# NanoRemotev2.net
KiCad netlist of a schematic drawn in EAGLE
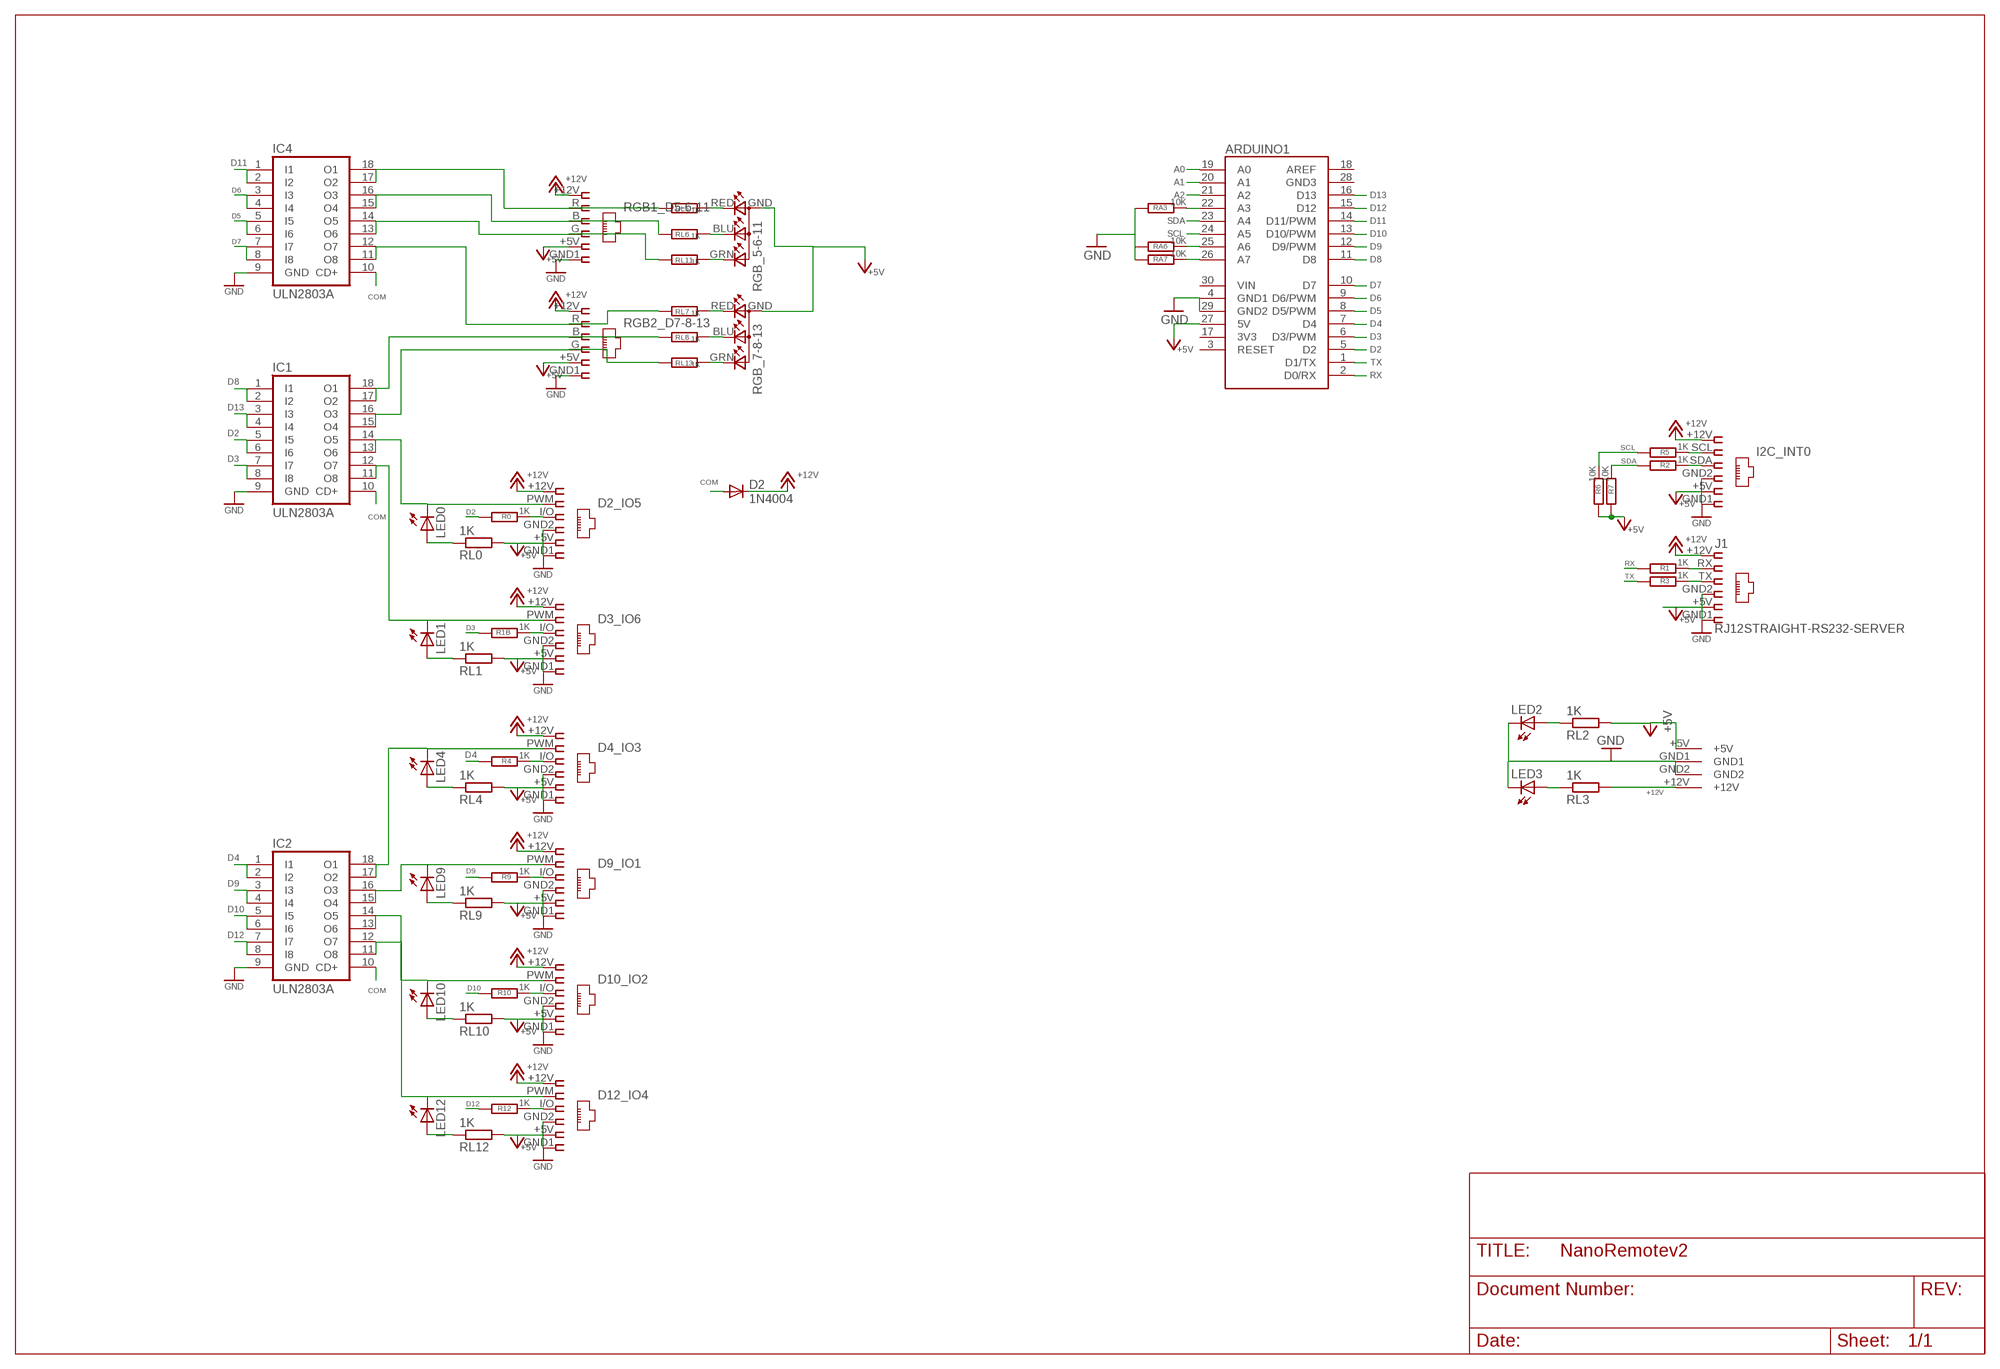
[diagram p0: schematic, sheet 1]

(export (version "E")
  (design (tool "Eeschema 10.0.6"))
  (components
    (comp (ref "ARDUINO1")
      (value "ARDUINO_NANO")
      (footprint "eagle-import:ARDUINO_NANO")
      (libsource (lib "eagle-import") (part "ARDUINO_NANO"))
    )
    (comp (ref "D2")
      (value "1N4004")
      (footprint "eagle-import:DO41-10")
      (libsource (lib "eagle-import") (part "1N4004"))
    )
    (comp (ref "D2_IO5")
      (value "IO5")
      (footprint "eagle-import:RJ12-STRAIGHT")
      (libsource (lib "eagle-import") (part "RJ12STRAIGHT"))
    )
    (comp (ref "D3_IO6")
      (value "IO6")
      (footprint "eagle-import:RJ12-STRAIGHT")
      (libsource (lib "eagle-import") (part "RJ12STRAIGHT"))
    )
    (comp (ref "D4_IO3")
      (value "IO3")
      (footprint "eagle-import:RJ12-STRAIGHT")
      (libsource (lib "eagle-import") (part "RJ12STRAIGHT"))
    )
    (comp (ref "D9_IO1")
      (value "IO1")
      (footprint "eagle-import:RJ12-STRAIGHT")
      (libsource (lib "eagle-import") (part "RJ12STRAIGHT"))
    )
    (comp (ref "D10_IO2")
      (value "IO2")
      (footprint "eagle-import:RJ12-STRAIGHT")
      (libsource (lib "eagle-import") (part "RJ12STRAIGHT"))
    )
    (comp (ref "D12_IO4")
      (value "IO4")
      (footprint "eagle-import:RJ12-STRAIGHT")
      (libsource (lib "eagle-import") (part "RJ12STRAIGHT"))
    )
    (comp (ref "I2C_INT0")
      (value "I2C")
      (footprint "eagle-import:RJ12-STRAIGHT-I2C")
      (libsource (lib "eagle-import") (part "RJ12STRAIGHT-I2C"))
    )
    (comp (ref "IC1")
      (value "ULN2803A")
      (footprint "eagle-import:SO18W")
      (libsource (lib "eagle-import") (part "ULN2803A"))
    )
    (comp (ref "IC2")
      (value "ULN2803A")
      (footprint "eagle-import:SO18W")
      (libsource (lib "eagle-import") (part "ULN2803A"))
    )
    (comp (ref "IC4")
      (value "ULN2803A")
      (footprint "eagle-import:SO18W")
      (libsource (lib "eagle-import") (part "ULN2803A"))
    )
    (comp (ref "J1")
      (value "RJ12STRAIGHT-RS232-SERVER")
      (footprint "eagle-import:RJ12-STRAIGHT-RS232")
      (libsource (lib "eagle-import") (part "RJ12STRAIGHT-RS232-SERVER"))
    )
    (comp (ref "LED0")
      (value "LED3MM")
      (footprint "eagle-import:LED3MM")
      (libsource (lib "eagle-import") (part "LED3MM"))
    )
    (comp (ref "LED1")
      (value "LED3MM")
      (footprint "eagle-import:LED3MM")
      (libsource (lib "eagle-import") (part "LED3MM"))
    )
    (comp (ref "LED2")
      (value "LED3MM")
      (footprint "eagle-import:LED3MM")
      (libsource (lib "eagle-import") (part "LED3MM"))
    )
    (comp (ref "LED3")
      (value "LED3MM")
      (footprint "eagle-import:LED3MM")
      (libsource (lib "eagle-import") (part "LED3MM"))
    )
    (comp (ref "LED4")
      (value "LED3MM")
      (footprint "eagle-import:LED3MM")
      (libsource (lib "eagle-import") (part "LED3MM"))
    )
    (comp (ref "LED9")
      (value "LED3MM")
      (footprint "eagle-import:LED3MM")
      (libsource (lib "eagle-import") (part "LED3MM"))
    )
    (comp (ref "LED10")
      (value "LED3MM")
      (footprint "eagle-import:LED3MM")
      (libsource (lib "eagle-import") (part "LED3MM"))
    )
    (comp (ref "LED12")
      (value "LED3MM")
      (footprint "eagle-import:LED3MM")
      (libsource (lib "eagle-import") (part "LED3MM"))
    )
    (comp (ref "R0")
      (value "1K")
      (footprint "eagle-import:M1206")
      (libsource (lib "eagle-import") (part "R-EU_M1206"))
    )
    (comp (ref "R1")
      (value "1K")
      (footprint "eagle-import:M1206")
      (libsource (lib "eagle-import") (part "R-EU_M1206"))
    )
    (comp (ref "R1B")
      (value "1K")
      (footprint "eagle-import:M1206")
      (libsource (lib "eagle-import") (part "R-EU_M1206"))
    )
    (comp (ref "R2")
      (value "1K")
      (footprint "eagle-import:M1206")
      (libsource (lib "eagle-import") (part "R-EU_M1206"))
    )
    (comp (ref "R3")
      (value "1K")
      (footprint "eagle-import:M1206")
      (libsource (lib "eagle-import") (part "R-EU_M1206"))
    )
    (comp (ref "R4")
      (value "1K")
      (footprint "eagle-import:M1206")
      (libsource (lib "eagle-import") (part "R-EU_M1206"))
    )
    (comp (ref "R5")
      (value "1K")
      (footprint "eagle-import:M1206")
      (libsource (lib "eagle-import") (part "R-EU_M1206"))
    )
    (comp (ref "R6")
      (value "10K")
      (footprint "eagle-import:M1206")
      (libsource (lib "eagle-import") (part "R-EU_M1206"))
    )
    (comp (ref "R7")
      (value "10K")
      (footprint "eagle-import:M1206")
      (libsource (lib "eagle-import") (part "R-EU_M1206"))
    )
    (comp (ref "R9")
      (value "1K")
      (footprint "eagle-import:M1206")
      (libsource (lib "eagle-import") (part "R-EU_M1206"))
    )
    (comp (ref "R10")
      (value "1K")
      (footprint "eagle-import:M1206")
      (libsource (lib "eagle-import") (part "R-EU_M1206"))
    )
    (comp (ref "R12")
      (value "1K")
      (footprint "eagle-import:M1206")
      (libsource (lib "eagle-import") (part "R-EU_M1206"))
    )
    (comp (ref "RA3")
      (value "10K")
      (footprint "eagle-import:M1206")
      (libsource (lib "eagle-import") (part "R-EU_M1206"))
    )
    (comp (ref "RA6")
      (value "10K")
      (footprint "eagle-import:M1206")
      (libsource (lib "eagle-import") (part "R-EU_M1206"))
    )
    (comp (ref "RA7")
      (value "10K")
      (footprint "eagle-import:M1206")
      (libsource (lib "eagle-import") (part "R-EU_M1206"))
    )
    (comp (ref "RGB1_D5-6-11")
      (value "RGB1")
      (footprint "eagle-import:RJ12-STRAIGHT-RGB")
      (libsource (lib "eagle-import") (part "RJ12STRAIGHT-RGB"))
    )
    (comp (ref "RGB2_D7-8-13")
      (value "RGB2")
      (footprint "eagle-import:RJ12-STRAIGHT-RGB")
      (libsource (lib "eagle-import") (part "RJ12STRAIGHT-RGB"))
    )
    (comp (ref "RGB_5-6-11")
      (value "TOPLED-3")
      (footprint "eagle-import:LED-TRICOLOR-THROUGHHOLE")
      (libsource (lib "eagle-import") (part "TOPLED-3"))
    )
    (comp (ref "RGB_7-8-13")
      (value "TOPLED-3")
      (footprint "eagle-import:LED-TRICOLOR-THROUGHHOLE")
      (libsource (lib "eagle-import") (part "TOPLED-3"))
    )
    (comp (ref "RL0")
      (value "1K")
      (footprint "eagle-import:M1206")
      (libsource (lib "eagle-import") (part "R-EU_M1206"))
    )
    (comp (ref "RL1")
      (value "1K")
      (footprint "eagle-import:M1206")
      (libsource (lib "eagle-import") (part "R-EU_M1206"))
    )
    (comp (ref "RL2")
      (value "1K")
      (footprint "eagle-import:M1206")
      (libsource (lib "eagle-import") (part "R-EU_M1206"))
    )
    (comp (ref "RL3")
      (value "1K")
      (footprint "eagle-import:M1206")
      (libsource (lib "eagle-import") (part "R-EU_M1206"))
    )
    (comp (ref "RL4")
      (value "1K")
      (footprint "eagle-import:M1206")
      (libsource (lib "eagle-import") (part "R-EU_M1206"))
    )
    (comp (ref "RL5")
      (value "1K")
      (footprint "eagle-import:M1206")
      (libsource (lib "eagle-import") (part "R-EU_M1206"))
    )
    (comp (ref "RL6")
      (value "1K")
      (footprint "eagle-import:M1206")
      (libsource (lib "eagle-import") (part "R-EU_M1206"))
    )
    (comp (ref "RL7")
      (value "1K")
      (footprint "eagle-import:M1206")
      (libsource (lib "eagle-import") (part "R-EU_M1206"))
    )
    (comp (ref "RL8")
      (value "1K")
      (footprint "eagle-import:M1206")
      (libsource (lib "eagle-import") (part "R-EU_M1206"))
    )
    (comp (ref "RL9")
      (value "1K")
      (footprint "eagle-import:M1206")
      (libsource (lib "eagle-import") (part "R-EU_M1206"))
    )
    (comp (ref "RL10")
      (value "1K")
      (footprint "eagle-import:M1206")
      (libsource (lib "eagle-import") (part "R-EU_M1206"))
    )
    (comp (ref "RL11")
      (value "1K")
      (footprint "eagle-import:M1206")
      (libsource (lib "eagle-import") (part "R-EU_M1206"))
    )
    (comp (ref "RL12")
      (value "1K")
      (footprint "eagle-import:M1206")
      (libsource (lib "eagle-import") (part "R-EU_M1206"))
    )
    (comp (ref "RL13")
      (value "1K")
      (footprint "eagle-import:M1206")
      (libsource (lib "eagle-import") (part "R-EU_M1206"))
    )
    (comp (ref "U$1")
      (value "KPJX-4S-S")
      (footprint "eagle-import:KPJX-4S-S")
      (libsource (lib "eagle-import") (part "KPJX-4S-S"))
    )
  )
  (nets
    (net (code "1") (name "+5V") (class "Default")
      (node (ref "ARDUINO1") (pin "27") (pinfunction "5V_27") (pintype "power_in"))
      (node (ref "D10_IO2") (pin "+5V") (pinfunction "5_+5V") (pintype "power_in"))
      (node (ref "D12_IO4") (pin "+5V") (pinfunction "5_+5V") (pintype "power_in"))
      (node (ref "D2_IO5") (pin "+5V") (pinfunction "5_+5V") (pintype "power_in"))
      (node (ref "D3_IO6") (pin "+5V") (pinfunction "5_+5V") (pintype "power_in"))
      (node (ref "D4_IO3") (pin "+5V") (pinfunction "5_+5V") (pintype "power_in"))
      (node (ref "D9_IO1") (pin "+5V") (pinfunction "5_+5V") (pintype "power_in"))
      (node (ref "I2C_INT0") (pin "+5V") (pinfunction "5_+5V") (pintype "power_in"))
      (node (ref "J1") (pin "+5V") (pinfunction "5_+5V") (pintype "power_in"))
      (node (ref "R6") (pin "2") (pinfunction "2_2") (pintype "passive"))
      (node (ref "R7") (pin "2") (pinfunction "2_2") (pintype "passive"))
      (node (ref "RGB1_D5-6-11") (pin "+5V") (pinfunction "5_+5V") (pintype "power_in"))
      (node (ref "RGB2_D7-8-13") (pin "+5V") (pinfunction "5_+5V") (pintype "power_in"))
      (node (ref "RGB_5-6-11") (pin "GND") (pinfunction "A2_GND") (pintype "passive"))
      (node (ref "RGB_7-8-13") (pin "GND") (pinfunction "A2_GND") (pintype "passive"))
      (node (ref "RL0") (pin "2") (pinfunction "2_2") (pintype "passive"))
      (node (ref "RL1") (pin "2") (pinfunction "2_2") (pintype "passive"))
      (node (ref "RL10") (pin "2") (pinfunction "2_2") (pintype "passive"))
      (node (ref "RL12") (pin "2") (pinfunction "2_2") (pintype "passive"))
      (node (ref "RL2") (pin "2") (pinfunction "2_2") (pintype "passive"))
      (node (ref "RL4") (pin "2") (pinfunction "2_2") (pintype "passive"))
      (node (ref "RL9") (pin "2") (pinfunction "2_2") (pintype "passive"))
      (node (ref "U$1") (pin "+5V") (pinfunction "+5V_+5V") (pintype "power_in"))
    )
    (net (code "2") (name "+12V") (class "Default")
      (node (ref "D10_IO2") (pin "+12V") (pinfunction "1_+12V") (pintype "power_in"))
      (node (ref "D12_IO4") (pin "+12V") (pinfunction "1_+12V") (pintype "power_in"))
      (node (ref "D2") (pin "C") (pinfunction "C_C") (pintype "passive"))
      (node (ref "D2_IO5") (pin "+12V") (pinfunction "1_+12V") (pintype "power_in"))
      (node (ref "D3_IO6") (pin "+12V") (pinfunction "1_+12V") (pintype "power_in"))
      (node (ref "D4_IO3") (pin "+12V") (pinfunction "1_+12V") (pintype "power_in"))
      (node (ref "D9_IO1") (pin "+12V") (pinfunction "1_+12V") (pintype "power_in"))
      (node (ref "I2C_INT0") (pin "+12V") (pinfunction "1_+12V") (pintype "power_in"))
      (node (ref "J1") (pin "+12V") (pinfunction "1_+12V") (pintype "power_in"))
      (node (ref "RGB1_D5-6-11") (pin "+12V") (pinfunction "1_+12V") (pintype "power_in"))
      (node (ref "RGB2_D7-8-13") (pin "+12V") (pinfunction "1_+12V") (pintype "power_in"))
      (node (ref "RL3") (pin "2") (pinfunction "2_2") (pintype "passive"))
      (node (ref "U$1") (pin "+12V") (pinfunction "+12V_+12V") (pintype "power_in"))
    )
    (net (code "3") (name "/3V3") (class "Default")
      (node (ref "ARDUINO1") (pin "17") (pinfunction "3V3_17") (pintype "power_in"))
    )
    (net (code "4") (name "/A0") (class "Default")
      (node (ref "ARDUINO1") (pin "19") (pinfunction "A0_19") (pintype "bidirectional"))
    )
    (net (code "5") (name "/A1") (class "Default")
      (node (ref "ARDUINO1") (pin "20") (pinfunction "A1_20") (pintype "bidirectional"))
    )
    (net (code "6") (name "/A2") (class "Default")
      (node (ref "ARDUINO1") (pin "21") (pinfunction "A2_21") (pintype "bidirectional"))
    )
    (net (code "7") (name "/COM") (class "Default")
      (node (ref "D2") (pin "A") (pinfunction "A_A") (pintype "passive"))
      (node (ref "IC1") (pin "10") (pinfunction "CD+_10") (pintype "passive"))
      (node (ref "IC2") (pin "10") (pinfunction "CD+_10") (pintype "passive"))
      (node (ref "IC4") (pin "10") (pinfunction "CD+_10") (pintype "passive"))
    )
    (net (code "8") (name "/D2") (class "Default")
      (node (ref "ARDUINO1") (pin "5") (pinfunction "D2_5") (pintype "bidirectional"))
      (node (ref "IC1") (pin "5") (pinfunction "I5_5") (pintype "input"))
      (node (ref "IC1") (pin "6") (pinfunction "I6_6") (pintype "input"))
      (node (ref "R0") (pin "2") (pinfunction "2_2") (pintype "passive"))
    )
    (net (code "9") (name "/D3") (class "Default")
      (node (ref "ARDUINO1") (pin "6") (pinfunction "D3/PWM_6") (pintype "bidirectional"))
      (node (ref "IC1") (pin "7") (pinfunction "I7_7") (pintype "input"))
      (node (ref "IC1") (pin "8") (pinfunction "I8_8") (pintype "input"))
      (node (ref "R1B") (pin "2") (pinfunction "2_2") (pintype "passive"))
    )
    (net (code "10") (name "/D4") (class "Default")
      (node (ref "ARDUINO1") (pin "7") (pinfunction "D4_7") (pintype "bidirectional"))
      (node (ref "IC2") (pin "1") (pinfunction "I1_1") (pintype "input"))
      (node (ref "IC2") (pin "2") (pinfunction "I2_2") (pintype "input"))
      (node (ref "R4") (pin "2") (pinfunction "2_2") (pintype "passive"))
    )
    (net (code "11") (name "/D5") (class "Default")
      (node (ref "ARDUINO1") (pin "8") (pinfunction "D5/PWM_8") (pintype "bidirectional"))
      (node (ref "IC4") (pin "5") (pinfunction "I5_5") (pintype "input"))
      (node (ref "IC4") (pin "6") (pinfunction "I6_6") (pintype "input"))
    )
    (net (code "12") (name "/D6") (class "Default")
      (node (ref "ARDUINO1") (pin "9") (pinfunction "D6/PWM_9") (pintype "bidirectional"))
      (node (ref "IC4") (pin "3") (pinfunction "I3_3") (pintype "input"))
      (node (ref "IC4") (pin "4") (pinfunction "I4_4") (pintype "input"))
    )
    (net (code "13") (name "/D7") (class "Default")
      (node (ref "ARDUINO1") (pin "10") (pinfunction "D7_10") (pintype "bidirectional"))
      (node (ref "IC4") (pin "7") (pinfunction "I7_7") (pintype "input"))
      (node (ref "IC4") (pin "8") (pinfunction "I8_8") (pintype "input"))
    )
    (net (code "14") (name "/D8") (class "Default")
      (node (ref "ARDUINO1") (pin "11") (pinfunction "D8_11") (pintype "bidirectional"))
      (node (ref "IC1") (pin "1") (pinfunction "I1_1") (pintype "input"))
      (node (ref "IC1") (pin "2") (pinfunction "I2_2") (pintype "input"))
    )
    (net (code "15") (name "/D9") (class "Default")
      (node (ref "ARDUINO1") (pin "12") (pinfunction "D9/PWM_12") (pintype "bidirectional"))
      (node (ref "IC2") (pin "3") (pinfunction "I3_3") (pintype "input"))
      (node (ref "IC2") (pin "4") (pinfunction "I4_4") (pintype "input"))
      (node (ref "R9") (pin "2") (pinfunction "2_2") (pintype "passive"))
    )
    (net (code "16") (name "/D10") (class "Default")
      (node (ref "ARDUINO1") (pin "13") (pinfunction "D10/PWM_13") (pintype "bidirectional"))
      (node (ref "IC2") (pin "5") (pinfunction "I5_5") (pintype "input"))
      (node (ref "IC2") (pin "6") (pinfunction "I6_6") (pintype "input"))
      (node (ref "R10") (pin "2") (pinfunction "2_2") (pintype "passive"))
    )
    (net (code "17") (name "/D11") (class "Default")
      (node (ref "ARDUINO1") (pin "14") (pinfunction "D11/PWM_14") (pintype "bidirectional"))
      (node (ref "IC4") (pin "1") (pinfunction "I1_1") (pintype "input"))
      (node (ref "IC4") (pin "2") (pinfunction "I2_2") (pintype "input"))
    )
    (net (code "18") (name "/D12") (class "Default")
      (node (ref "ARDUINO1") (pin "15") (pinfunction "D12_15") (pintype "bidirectional"))
      (node (ref "IC2") (pin "7") (pinfunction "I7_7") (pintype "input"))
      (node (ref "IC2") (pin "8") (pinfunction "I8_8") (pintype "input"))
      (node (ref "R12") (pin "2") (pinfunction "2_2") (pintype "passive"))
    )
    (net (code "19") (name "/D13") (class "Default")
      (node (ref "ARDUINO1") (pin "16") (pinfunction "D13_16") (pintype "bidirectional"))
      (node (ref "IC1") (pin "3") (pinfunction "I3_3") (pintype "input"))
      (node (ref "IC1") (pin "4") (pinfunction "I4_4") (pintype "input"))
    )
    (net (code "20") (name "/RX") (class "Default")
      (node (ref "ARDUINO1") (pin "2") (pinfunction "D0/RX_2") (pintype "bidirectional"))
      (node (ref "R1") (pin "2") (pinfunction "2_2") (pintype "passive"))
    )
    (net (code "21") (name "/SCL") (class "Default")
      (node (ref "ARDUINO1") (pin "24") (pinfunction "A5_24") (pintype "bidirectional"))
      (node (ref "R5") (pin "2") (pinfunction "2_2") (pintype "passive"))
      (node (ref "R6") (pin "1") (pinfunction "1_1") (pintype "passive"))
    )
    (net (code "22") (name "/SDA") (class "Default")
      (node (ref "ARDUINO1") (pin "23") (pinfunction "A4_23") (pintype "bidirectional"))
      (node (ref "R2") (pin "2") (pinfunction "2_2") (pintype "passive"))
      (node (ref "R7") (pin "1") (pinfunction "1_1") (pintype "passive"))
    )
    (net (code "23") (name "/TX") (class "Default")
      (node (ref "ARDUINO1") (pin "1") (pinfunction "D1/TX_1") (pintype "bidirectional"))
      (node (ref "R3") (pin "2") (pinfunction "2_2") (pintype "passive"))
    )
    (net (code "24") (name "GND") (class "Default")
      (node (ref "ARDUINO1") (pin "29") (pinfunction "GND2_29") (pintype "power_in"))
      (node (ref "ARDUINO1") (pin "4") (pinfunction "GND1_4") (pintype "power_in"))
      (node (ref "D10_IO2") (pin "GND1") (pinfunction "6_GND1") (pintype "power_in"))
      (node (ref "D10_IO2") (pin "GND2") (pinfunction "4_GND2") (pintype "power_in"))
      (node (ref "D12_IO4") (pin "GND1") (pinfunction "6_GND1") (pintype "power_in"))
      (node (ref "D12_IO4") (pin "GND2") (pinfunction "4_GND2") (pintype "power_in"))
      (node (ref "D2_IO5") (pin "GND1") (pinfunction "6_GND1") (pintype "power_in"))
      (node (ref "D2_IO5") (pin "GND2") (pinfunction "4_GND2") (pintype "power_in"))
      (node (ref "D3_IO6") (pin "GND1") (pinfunction "6_GND1") (pintype "power_in"))
      (node (ref "D3_IO6") (pin "GND2") (pinfunction "4_GND2") (pintype "power_in"))
      (node (ref "D4_IO3") (pin "GND1") (pinfunction "6_GND1") (pintype "power_in"))
      (node (ref "D4_IO3") (pin "GND2") (pinfunction "4_GND2") (pintype "power_in"))
      (node (ref "D9_IO1") (pin "GND1") (pinfunction "6_GND1") (pintype "power_in"))
      (node (ref "D9_IO1") (pin "GND2") (pinfunction "4_GND2") (pintype "power_in"))
      (node (ref "I2C_INT0") (pin "GND1") (pinfunction "6_GND1") (pintype "power_in"))
      (node (ref "I2C_INT0") (pin "GND2") (pinfunction "4_GND2") (pintype "power_in"))
      (node (ref "IC1") (pin "9") (pinfunction "GND_9") (pintype "power_in"))
      (node (ref "IC2") (pin "9") (pinfunction "GND_9") (pintype "power_in"))
      (node (ref "IC4") (pin "9") (pinfunction "GND_9") (pintype "power_in"))
      (node (ref "J1") (pin "GND1") (pinfunction "6_GND1") (pintype "power_in"))
      (node (ref "J1") (pin "GND2") (pinfunction "4_GND2") (pintype "power_in"))
      (node (ref "LED2") (pin "K") (pinfunction "C_K") (pintype "passive"))
      (node (ref "LED3") (pin "K") (pinfunction "C_K") (pintype "passive"))
      (node (ref "RA3") (pin "2") (pinfunction "2_2") (pintype "passive"))
      (node (ref "RA6") (pin "2") (pinfunction "2_2") (pintype "passive"))
      (node (ref "RA7") (pin "2") (pinfunction "2_2") (pintype "passive"))
      (node (ref "RGB1_D5-6-11") (pin "GND1") (pinfunction "6_GND1") (pintype "power_in"))
      (node (ref "RGB2_D7-8-13") (pin "GND1") (pinfunction "6_GND1") (pintype "power_in"))
      (node (ref "U$1") (pin "GND1") (pinfunction "GND1_GND1") (pintype "input"))
      (node (ref "U$1") (pin "GND2") (pinfunction "GND2_GND2") (pintype "input"))
    )
    (net (code "25") (name "Net-(ARDUINO1-A3)") (class "Default")
      (node (ref "ARDUINO1") (pin "22") (pinfunction "A3_22") (pintype "bidirectional"))
      (node (ref "RA3") (pin "1") (pinfunction "1_1") (pintype "passive"))
    )
    (net (code "26") (name "Net-(ARDUINO1-A6)") (class "Default")
      (node (ref "ARDUINO1") (pin "25") (pinfunction "A6_25") (pintype "bidirectional"))
      (node (ref "RA6") (pin "1") (pinfunction "1_1") (pintype "passive"))
    )
    (net (code "27") (name "Net-(ARDUINO1-A7)") (class "Default")
      (node (ref "ARDUINO1") (pin "26") (pinfunction "A7_26") (pintype "bidirectional"))
      (node (ref "RA7") (pin "1") (pinfunction "1_1") (pintype "passive"))
    )
    (net (code "28") (name "Net-(D2_IO5-2)") (class "Default")
      (node (ref "D2_IO5") (pin "PWM") (pinfunction "2_PWM") (pintype "bidirectional"))
      (node (ref "IC1") (pin "13") (pinfunction "O6_13") (pintype "open_collector"))
      (node (ref "IC1") (pin "14") (pinfunction "O5_14") (pintype "open_collector"))
      (node (ref "LED0") (pin "K") (pinfunction "C_K") (pintype "passive"))
    )
    (net (code "29") (name "Net-(D2_IO5-3)") (class "Default")
      (node (ref "D2_IO5") (pin "I/O") (pinfunction "3_I/O") (pintype "bidirectional"))
      (node (ref "R0") (pin "1") (pinfunction "1_1") (pintype "passive"))
    )
    (net (code "30") (name "Net-(D3_IO6-2)") (class "Default")
      (node (ref "D3_IO6") (pin "PWM") (pinfunction "2_PWM") (pintype "bidirectional"))
      (node (ref "IC1") (pin "11") (pinfunction "O8_11") (pintype "open_collector"))
      (node (ref "IC1") (pin "12") (pinfunction "O7_12") (pintype "open_collector"))
      (node (ref "LED1") (pin "K") (pinfunction "C_K") (pintype "passive"))
    )
    (net (code "31") (name "Net-(D3_IO6-3)") (class "Default")
      (node (ref "D3_IO6") (pin "I/O") (pinfunction "3_I/O") (pintype "bidirectional"))
      (node (ref "R1B") (pin "1") (pinfunction "1_1") (pintype "passive"))
    )
    (net (code "32") (name "Net-(D4_IO3-2)") (class "Default")
      (node (ref "D4_IO3") (pin "PWM") (pinfunction "2_PWM") (pintype "bidirectional"))
      (node (ref "IC2") (pin "17") (pinfunction "O2_17") (pintype "open_collector"))
      (node (ref "IC2") (pin "18") (pinfunction "O1_18") (pintype "open_collector"))
      (node (ref "LED4") (pin "K") (pinfunction "C_K") (pintype "passive"))
    )
    (net (code "33") (name "Net-(D4_IO3-3)") (class "Default")
      (node (ref "D4_IO3") (pin "I/O") (pinfunction "3_I/O") (pintype "bidirectional"))
      (node (ref "R4") (pin "1") (pinfunction "1_1") (pintype "passive"))
    )
    (net (code "34") (name "Net-(D9_IO1-2)") (class "Default")
      (node (ref "D9_IO1") (pin "PWM") (pinfunction "2_PWM") (pintype "bidirectional"))
      (node (ref "IC2") (pin "15") (pinfunction "O4_15") (pintype "open_collector"))
      (node (ref "IC2") (pin "16") (pinfunction "O3_16") (pintype "open_collector"))
      (node (ref "LED9") (pin "K") (pinfunction "C_K") (pintype "passive"))
    )
    (net (code "35") (name "Net-(D9_IO1-3)") (class "Default")
      (node (ref "D9_IO1") (pin "I/O") (pinfunction "3_I/O") (pintype "bidirectional"))
      (node (ref "R9") (pin "1") (pinfunction "1_1") (pintype "passive"))
    )
    (net (code "36") (name "Net-(D10_IO2-2)") (class "Default")
      (node (ref "D10_IO2") (pin "PWM") (pinfunction "2_PWM") (pintype "bidirectional"))
      (node (ref "IC2") (pin "13") (pinfunction "O6_13") (pintype "open_collector"))
      (node (ref "IC2") (pin "14") (pinfunction "O5_14") (pintype "open_collector"))
      (node (ref "LED10") (pin "K") (pinfunction "C_K") (pintype "passive"))
    )
    (net (code "37") (name "Net-(D10_IO2-3)") (class "Default")
      (node (ref "D10_IO2") (pin "I/O") (pinfunction "3_I/O") (pintype "bidirectional"))
      (node (ref "R10") (pin "1") (pinfunction "1_1") (pintype "passive"))
    )
    (net (code "38") (name "Net-(D12_IO4-2)") (class "Default")
      (node (ref "D12_IO4") (pin "PWM") (pinfunction "2_PWM") (pintype "bidirectional"))
      (node (ref "IC2") (pin "11") (pinfunction "O8_11") (pintype "open_collector"))
      (node (ref "IC2") (pin "12") (pinfunction "O7_12") (pintype "open_collector"))
      (node (ref "LED12") (pin "K") (pinfunction "C_K") (pintype "passive"))
    )
    (net (code "39") (name "Net-(D12_IO4-3)") (class "Default")
      (node (ref "D12_IO4") (pin "I/O") (pinfunction "3_I/O") (pintype "bidirectional"))
      (node (ref "R12") (pin "1") (pinfunction "1_1") (pintype "passive"))
    )
    (net (code "40") (name "Net-(I2C_INT0-2)") (class "Default")
      (node (ref "I2C_INT0") (pin "SCL") (pinfunction "2_SCL") (pintype "bidirectional"))
      (node (ref "R5") (pin "1") (pinfunction "1_1") (pintype "passive"))
    )
    (net (code "41") (name "Net-(I2C_INT0-3)") (class "Default")
      (node (ref "I2C_INT0") (pin "SDA") (pinfunction "3_SDA") (pintype "bidirectional"))
      (node (ref "R2") (pin "1") (pinfunction "1_1") (pintype "passive"))
    )
    (net (code "42") (name "Net-(IC1-O1)") (class "Default")
      (node (ref "IC1") (pin "17") (pinfunction "O2_17") (pintype "open_collector"))
      (node (ref "IC1") (pin "18") (pinfunction "O1_18") (pintype "open_collector"))
      (node (ref "RGB2_D7-8-13") (pin "B") (pinfunction "3_B") (pintype "bidirectional"))
      (node (ref "RL8") (pin "1") (pinfunction "1_1") (pintype "passive"))
    )
    (net (code "43") (name "Net-(IC1-O3)") (class "Default")
      (node (ref "IC1") (pin "15") (pinfunction "O4_15") (pintype "open_collector"))
      (node (ref "IC1") (pin "16") (pinfunction "O3_16") (pintype "open_collector"))
      (node (ref "RGB2_D7-8-13") (pin "G") (pinfunction "4_G") (pintype "power_in"))
      (node (ref "RL13") (pin "1") (pinfunction "1_1") (pintype "passive"))
    )
    (net (code "44") (name "Net-(IC4-O1)") (class "Default")
      (node (ref "IC4") (pin "17") (pinfunction "O2_17") (pintype "open_collector"))
      (node (ref "IC4") (pin "18") (pinfunction "O1_18") (pintype "open_collector"))
      (node (ref "RGB1_D5-6-11") (pin "R") (pinfunction "2_R") (pintype "bidirectional"))
      (node (ref "RL5") (pin "1") (pinfunction "1_1") (pintype "passive"))
    )
    (net (code "45") (name "Net-(IC4-O3)") (class "Default")
      (node (ref "IC4") (pin "15") (pinfunction "O4_15") (pintype "open_collector"))
      (node (ref "IC4") (pin "16") (pinfunction "O3_16") (pintype "open_collector"))
      (node (ref "RGB1_D5-6-11") (pin "B") (pinfunction "3_B") (pintype "bidirectional"))
      (node (ref "RL6") (pin "1") (pinfunction "1_1") (pintype "passive"))
    )
    (net (code "46") (name "Net-(IC4-O5)") (class "Default")
      (node (ref "IC4") (pin "13") (pinfunction "O6_13") (pintype "open_collector"))
      (node (ref "IC4") (pin "14") (pinfunction "O5_14") (pintype "open_collector"))
      (node (ref "RGB1_D5-6-11") (pin "G") (pinfunction "4_G") (pintype "power_in"))
      (node (ref "RL11") (pin "1") (pinfunction "1_1") (pintype "passive"))
    )
    (net (code "47") (name "Net-(IC4-O7)") (class "Default")
      (node (ref "IC4") (pin "11") (pinfunction "O8_11") (pintype "open_collector"))
      (node (ref "IC4") (pin "12") (pinfunction "O7_12") (pintype "open_collector"))
      (node (ref "RGB2_D7-8-13") (pin "R") (pinfunction "2_R") (pintype "bidirectional"))
      (node (ref "RL7") (pin "1") (pinfunction "1_1") (pintype "passive"))
    )
    (net (code "48") (name "Net-(J1-2)") (class "Default")
      (node (ref "J1") (pin "RX") (pinfunction "2_RX") (pintype "bidirectional"))
      (node (ref "R1") (pin "1") (pinfunction "1_1") (pintype "passive"))
    )
    (net (code "49") (name "Net-(J1-3)") (class "Default")
      (node (ref "J1") (pin "TX") (pinfunction "3_TX") (pintype "bidirectional"))
      (node (ref "R3") (pin "1") (pinfunction "1_1") (pintype "passive"))
    )
    (net (code "50") (name "Net-(LED0-PadA)") (class "Default")
      (node (ref "LED0") (pin "A") (pinfunction "A_A") (pintype "passive"))
      (node (ref "RL0") (pin "1") (pinfunction "1_1") (pintype "passive"))
    )
    (net (code "51") (name "Net-(LED1-PadA)") (class "Default")
      (node (ref "LED1") (pin "A") (pinfunction "A_A") (pintype "passive"))
      (node (ref "RL1") (pin "1") (pinfunction "1_1") (pintype "passive"))
    )
    (net (code "52") (name "Net-(LED2-PadA)") (class "Default")
      (node (ref "LED2") (pin "A") (pinfunction "A_A") (pintype "passive"))
      (node (ref "RL2") (pin "1") (pinfunction "1_1") (pintype "passive"))
    )
    (net (code "53") (name "Net-(LED3-PadA)") (class "Default")
      (node (ref "LED3") (pin "A") (pinfunction "A_A") (pintype "passive"))
      (node (ref "RL3") (pin "1") (pinfunction "1_1") (pintype "passive"))
    )
    (net (code "54") (name "Net-(LED4-PadA)") (class "Default")
      (node (ref "LED4") (pin "A") (pinfunction "A_A") (pintype "passive"))
      (node (ref "RL4") (pin "1") (pinfunction "1_1") (pintype "passive"))
    )
    (net (code "55") (name "Net-(LED9-PadA)") (class "Default")
      (node (ref "LED9") (pin "A") (pinfunction "A_A") (pintype "passive"))
      (node (ref "RL9") (pin "1") (pinfunction "1_1") (pintype "passive"))
    )
    (net (code "56") (name "Net-(LED10-PadA)") (class "Default")
      (node (ref "LED10") (pin "A") (pinfunction "A_A") (pintype "passive"))
      (node (ref "RL10") (pin "1") (pinfunction "1_1") (pintype "passive"))
    )
    (net (code "57") (name "Net-(LED12-PadA)") (class "Default")
      (node (ref "LED12") (pin "A") (pinfunction "A_A") (pintype "passive"))
      (node (ref "RL12") (pin "1") (pinfunction "1_1") (pintype "passive"))
    )
    (net (code "58") (name "Net-(RGB_5-6-11-CBLUE)") (class "Default")
      (node (ref "RGB_5-6-11") (pin "BLU") (pinfunction "CBLUE_BLU") (pintype "passive"))
      (node (ref "RL6") (pin "2") (pinfunction "2_2") (pintype "passive"))
    )
    (net (code "59") (name "Net-(RGB_5-6-11-CGREEN)") (class "Default")
      (node (ref "RGB_5-6-11") (pin "GRN") (pinfunction "CGREEN_GRN") (pintype "passive"))
      (node (ref "RL11") (pin "2") (pinfunction "2_2") (pintype "passive"))
    )
    (net (code "60") (name "Net-(RGB_5-6-11-CRED)") (class "Default")
      (node (ref "RGB_5-6-11") (pin "RED") (pinfunction "CRED_RED") (pintype "passive"))
      (node (ref "RL5") (pin "2") (pinfunction "2_2") (pintype "passive"))
    )
    (net (code "61") (name "Net-(RGB_7-8-13-CBLUE)") (class "Default")
      (node (ref "RGB_7-8-13") (pin "BLU") (pinfunction "CBLUE_BLU") (pintype "passive"))
      (node (ref "RL8") (pin "2") (pinfunction "2_2") (pintype "passive"))
    )
    (net (code "62") (name "Net-(RGB_7-8-13-CGREEN)") (class "Default")
      (node (ref "RGB_7-8-13") (pin "GRN") (pinfunction "CGREEN_GRN") (pintype "passive"))
      (node (ref "RL13") (pin "2") (pinfunction "2_2") (pintype "passive"))
    )
    (net (code "63") (name "Net-(RGB_7-8-13-CRED)") (class "Default")
      (node (ref "RGB_7-8-13") (pin "RED") (pinfunction "CRED_RED") (pintype "passive"))
      (node (ref "RL7") (pin "2") (pinfunction "2_2") (pintype "passive"))
    )
    (net (code "64") (name "unconnected-(ARDUINO1-AREF-Pad18)") (class "Default")
      (node (ref "ARDUINO1") (pin "18") (pinfunction "AREF_18") (pintype "bidirectional"))
    )
    (net (code "65") (name "unconnected-(ARDUINO1-GND3-Pad28)") (class "Default")
      (node (ref "ARDUINO1") (pin "28") (pinfunction "GND3_28") (pintype "bidirectional"))
    )
    (net (code "66") (name "unconnected-(ARDUINO1-RESET-Pad3)") (class "Default")
      (node (ref "ARDUINO1") (pin "3") (pinfunction "RESET_3") (pintype "bidirectional"))
    )
    (net (code "67") (name "unconnected-(ARDUINO1-VIN-Pad30)") (class "Default")
      (node (ref "ARDUINO1") (pin "30") (pinfunction "VIN_30") (pintype "bidirectional"))
    )
  )
)
